# Sheet1.net
KiCad netlist of a schematic drawn in Altium Designer
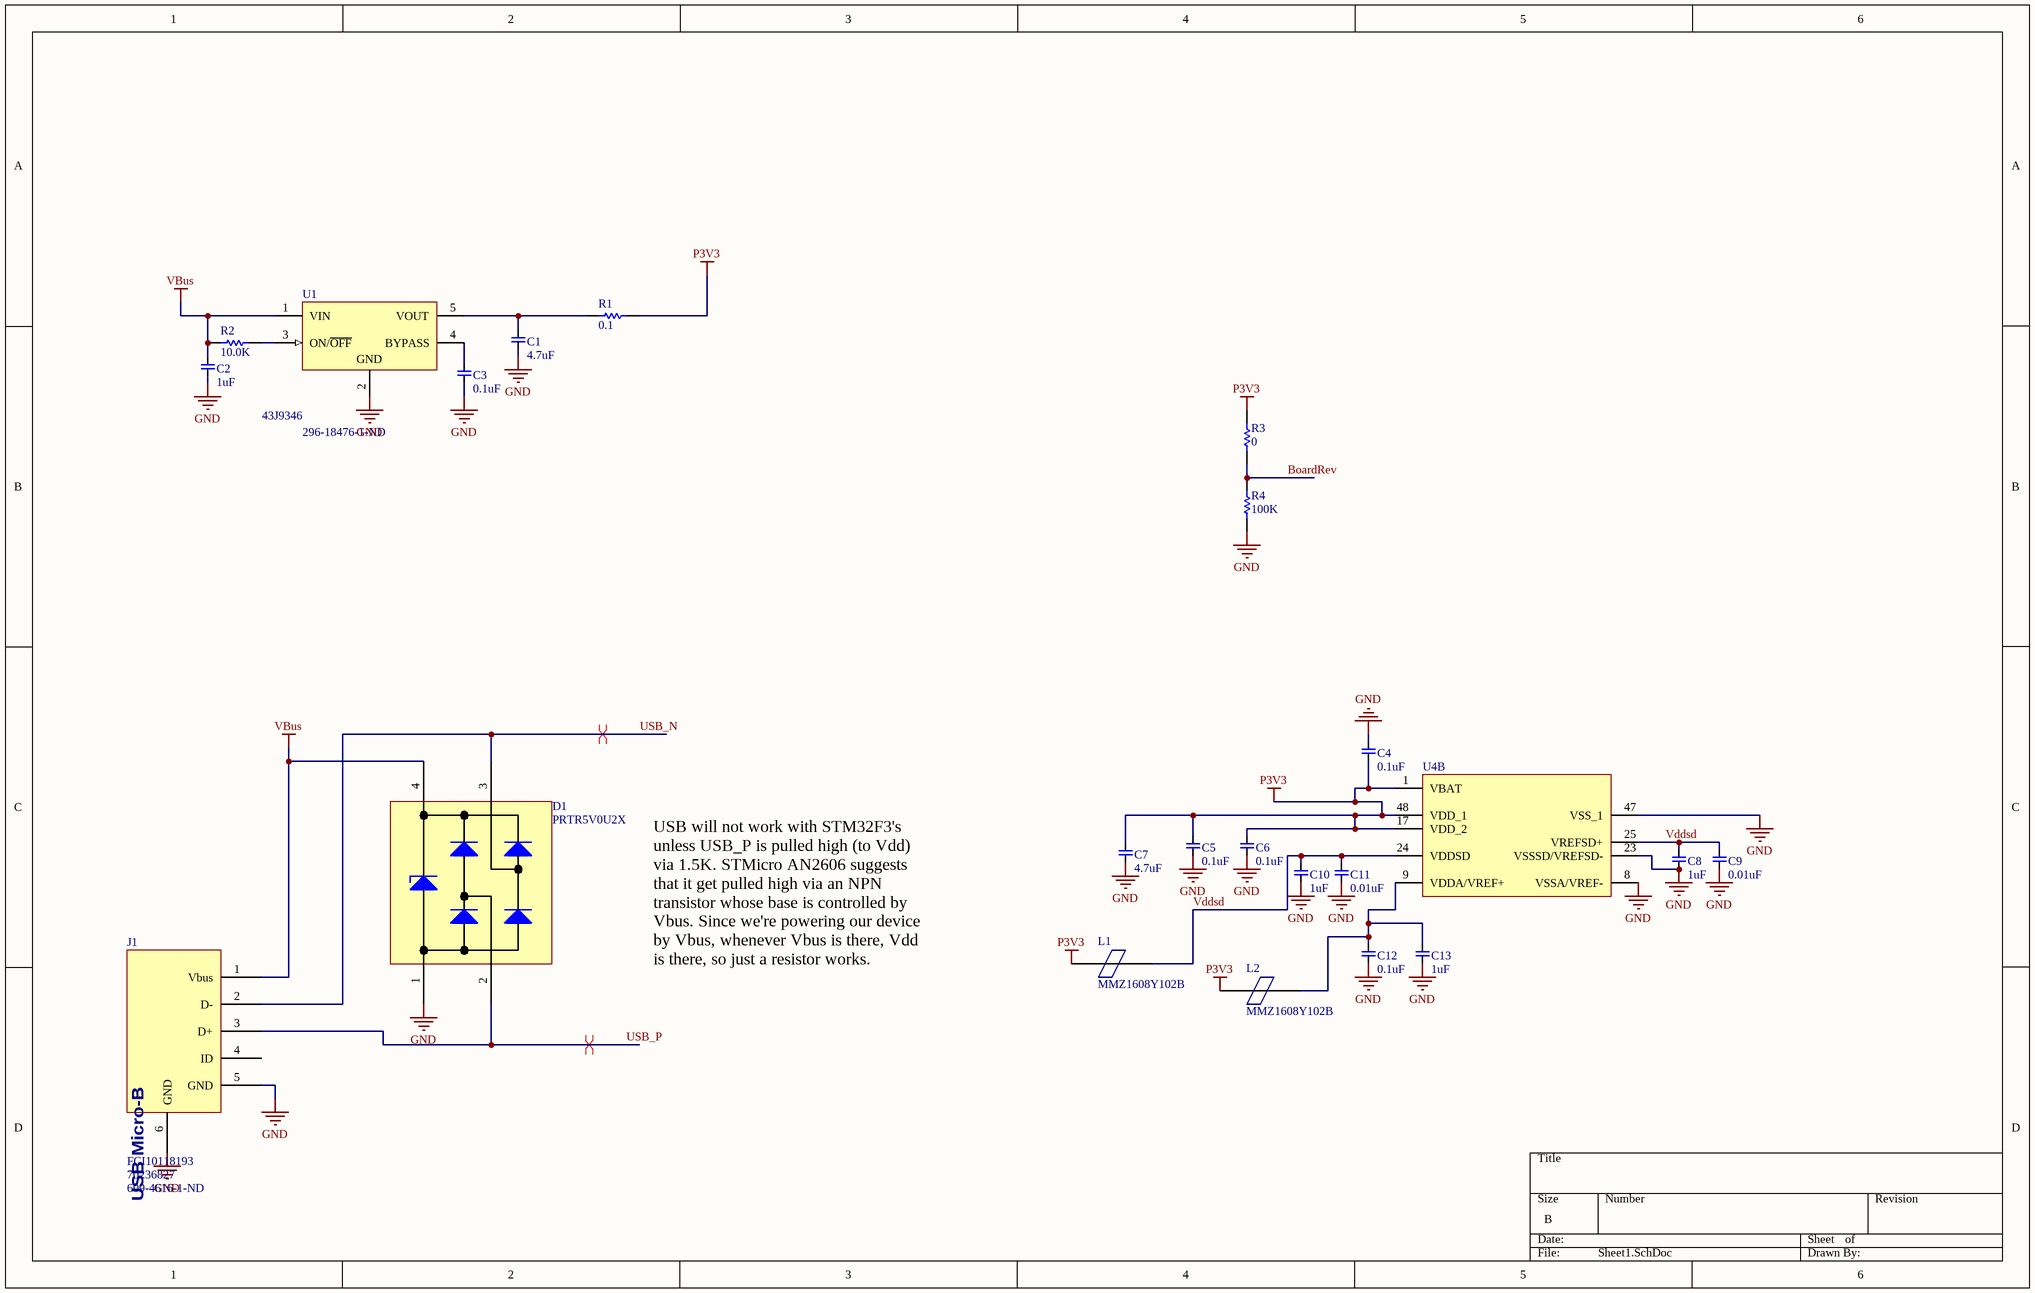
[diagram p0: Sheet1.SchDoc]

(export (version "E")
  (design (tool "Eeschema 10.0.6"))
  (components
    (comp (ref "C1")
      (value "4.7uF")
      (footprint "CAP0603")
      (description "CAP 4.7uF +/-10% 10V X6S 0603")
      (fields (field (name "TOLERANCE") "+/-10%") (field (name "VOLTAGE") "10V"))
      (libsource (lib "PassiveSMT") (part "Capacitor_np"))
    )
    (comp (ref "C2")
      (value "1uF")
      (footprint "CAP0402")
      (description "CAP 1uF +/-10% 10V X5R 0402")
      (fields (field (name "TOLERANCE") "+/-10%") (field (name "VOLTAGE") "10V"))
      (libsource (lib "PassiveSMT") (part "Capacitor_np"))
    )
    (comp (ref "C3")
      (value "0.1uF")
      (footprint "CAP0402")
      (description "CAP 0.1uF +/-10% 25V X7R 0402")
      (fields (field (name "TOLERANCE") "+/-10%") (field (name "VOLTAGE") "25V"))
      (libsource (lib "PassiveSMT") (part "Capacitor_np"))
    )
    (comp (ref "C4")
      (value "0.1uF")
      (footprint "CAP0402")
      (description "CAP 0.1uF +/-10% 25V X7R 0402")
      (fields (field (name "TOLERANCE") "+/-10%") (field (name "VOLTAGE") "25V"))
      (libsource (lib "PassiveSMT") (part "Capacitor_np"))
    )
    (comp (ref "C5")
      (value "0.1uF")
      (footprint "CAP0402")
      (description "CAP 0.1uF +/-10% 25V X7R 0402")
      (fields (field (name "TOLERANCE") "+/-10%") (field (name "VOLTAGE") "25V"))
      (libsource (lib "PassiveSMT") (part "Capacitor_np"))
    )
    (comp (ref "C6")
      (value "0.1uF")
      (footprint "CAP0402")
      (description "CAP 0.1uF +/-10% 25V X7R 0402")
      (fields (field (name "TOLERANCE") "+/-10%") (field (name "VOLTAGE") "25V"))
      (libsource (lib "PassiveSMT") (part "Capacitor_np"))
    )
    (comp (ref "C7")
      (value "4.7uF")
      (footprint "CAP0603")
      (description "CAP 4.7uF +/-10% 10V X6S 0603")
      (fields (field (name "TOLERANCE") "+/-10%") (field (name "VOLTAGE") "10V"))
      (libsource (lib "PassiveSMT") (part "Capacitor_np"))
    )
    (comp (ref "C8")
      (value "1uF")
      (footprint "CAP0603")
      (description "CAP 1uF +/-10% 25V X7R 0603")
      (fields (field (name "TOLERANCE") "+/-10%") (field (name "VOLTAGE") "25V"))
      (libsource (lib "PassiveSMT") (part "Capacitor_np"))
    )
    (comp (ref "C9")
      (value "0.01uF")
      (footprint "CAP0402")
      (description "CAP 0.01uF +/-20% 50V X6S 0402")
      (fields (field (name "TOLERANCE") "+/-20%") (field (name "VOLTAGE") "50V"))
      (libsource (lib "PassiveSMT") (part "Capacitor_np"))
    )
    (comp (ref "C10")
      (value "1uF")
      (footprint "CAP0603")
      (description "CAP 1uF +/-10% 25V X7R 0603")
      (fields (field (name "TOLERANCE") "+/-10%") (field (name "VOLTAGE") "25V"))
      (libsource (lib "PassiveSMT") (part "Capacitor_np"))
    )
    (comp (ref "C11")
      (value "0.01uF")
      (footprint "CAP0402")
      (description "CAP 0.01uF +/-20% 50V X6S 0402")
      (fields (field (name "TOLERANCE") "+/-20%") (field (name "VOLTAGE") "50V"))
      (libsource (lib "PassiveSMT") (part "Capacitor_np"))
    )
    (comp (ref "C12")
      (value "0.1uF")
      (footprint "CAP0402")
      (description "CAP 0.1uF +/-10% 25V X7R 0402")
      (fields (field (name "TOLERANCE") "+/-10%") (field (name "VOLTAGE") "25V"))
      (libsource (lib "PassiveSMT") (part "Capacitor_np"))
    )
    (comp (ref "C13")
      (value "1uF")
      (footprint "CAP0603")
      (description "CAP 1uF +/-10% 25V X7R 0603")
      (fields (field (name "TOLERANCE") "+/-10%") (field (name "VOLTAGE") "25V"))
      (libsource (lib "PassiveSMT") (part "Capacitor_np"))
    )
    (comp (ref "D1")
      (value "PRTR5V0U2X")
      (footprint "SOT190P230X110-4N")
      (description "Diode Array, ESD Protection 1pF USB2.0 SOT143")
      (fields (field (name "MANUFACTURER") "NXP Semiconductors"))
      (libsource (lib "MF_MiscLib") (part "PRTR5V0U2X"))
    )
    (comp (ref "J1")
      (value "FCI10118193")
      (footprint "FCI_10118193")
      (description "Connector Receptacle USB - micro B 2.0 5 Position Surface Mount, Right Angle, Horizontal")
      (fields
        (field (name "MANUFACTURER") "FCI")
        (field (name "SUPPLIER PART NUMBER 1") "70236827")
        (field (name "SUPPLIER PART NUMBER 2") "609-4616-1-ND")
      )
      (libsource (lib "MF_MiscLib") (part "CONN_USB_MICRO-B_HORIZ_TH"))
    )
    (comp (ref "L1")
      (value "MMZ1608Y102B")
      (footprint "INDC1608X06N")
      (description "Ferrite, 1000oh, 400mA, 0603")
      (libsource (lib "MF_MiscLib") (part "MMZ1608Y102B"))
    )
    (comp (ref "L2")
      (value "MMZ1608Y102B")
      (footprint "INDC1608X06N")
      (description "Ferrite, 1000oh, 400mA, 0603")
      (libsource (lib "MF_MiscLib") (part "MMZ1608Y102B"))
    )
    (comp (ref "R1")
      (value "0.1")
      (footprint "RES0402")
      (description "RES .1 OHM 1/6W 1% 0402 SMD")
      (fields (field (name "MANUFACTURER") "Panasonic"))
      (libsource (lib "MF_MiscLib") (part "0402_0.1ohm"))
    )
    (comp (ref "R2")
      (value "10.0K")
      (footprint "RES0402")
      (description "Resistor SMT 0402 10.0K 1% ohm")
      (fields (field (name "TOLERANCE") "1%") (field (name "POWER") "1/16W"))
      (libsource (lib "PassiveSMT") (part "Resistor1"))
    )
    (comp (ref "R3")
      (value "0")
      (footprint "RES0402")
      (description "Resistor SMT 0402 0 1% ohm")
      (fields (field (name "TOLERANCE") "1%") (field (name "POWER") "1/16W"))
      (libsource (lib "PassiveSMT") (part "Resistor1"))
    )
    (comp (ref "R4")
      (value "100K")
      (footprint "RES0402")
      (description "Resistor SMT 0402 100K 1% ohm")
      (fields (field (name "TOLERANCE") "1%") (field (name "POWER") "1/16W"))
      (libsource (lib "PassiveSMT") (part "Resistor1"))
    )
    (comp (ref "U1")
      (value "~")
      (footprint "TI-DBV5_N")
      (fields
        (field (name "MANUFACTURER") "Texas Instruments")
        (field (name "PARTNUMBER") "LP2985-33DBVR")
        (field (name "SUPPLIER PART NUMBER 1") "43J9346")
        (field (name "SUPPLIER PART NUMBER 2") "296-18476-1-ND")
      )
      (libsource (lib "MF_MiscLib") (part "LP2985-33DBVR"))
    )
    (comp (ref "U4")
      (value "~")
      (footprint "STM-LQFP48_N")
      (fields (field (name "PARTNUMBER") "STM32F373CCT6"))
      (libsource (lib "STMicroelectronics_STM32_F3") (part "STM32F373CCT6"))
    )
  )
  (nets
    (net (code "1") (name "/BoardRev") (class "Default")
      (node (ref "R3") (pin "1") (pinfunction "1_1") (pintype "passive"))
      (node (ref "R4") (pin "2") (pinfunction "2_2") (pintype "passive"))
    )
    (net (code "2") (name "/USB_N") (class "Default")
      (node (ref "D1") (pin "3") (pinfunction "3_3") (pintype "passive"))
      (node (ref "J1") (pin "2") (pinfunction "D-_2") (pintype "passive"))
    )
    (net (code "3") (name "/USB_P") (class "Default")
      (node (ref "D1") (pin "2") (pinfunction "2_2") (pintype "passive"))
      (node (ref "J1") (pin "3") (pinfunction "D+_3") (pintype "passive"))
    )
    (net (code "4") (name "/Vddsd") (class "Default")
      (node (ref "C10") (pin "2") (pinfunction "2_2") (pintype "passive"))
      (node (ref "C11") (pin "2") (pinfunction "2_2") (pintype "passive"))
      (node (ref "C8") (pin "2") (pinfunction "2_2") (pintype "passive"))
      (node (ref "C9") (pin "2") (pinfunction "2_2") (pintype "passive"))
      (node (ref "L1") (pin "2") (pinfunction "2_2") (pintype "passive"))
      (node (ref "U4") (pin "24") (pinfunction "VDDSD_24") (pintype "power_in"))
      (node (ref "U4") (pin "25") (pinfunction "VREFSD+_25") (pintype "power_in"))
    )
    (net (code "5") (name "GND") (class "Default")
      (node (ref "C1") (pin "1") (pinfunction "1_1") (pintype "passive"))
      (node (ref "C10") (pin "1") (pinfunction "1_1") (pintype "passive"))
      (node (ref "C11") (pin "1") (pinfunction "1_1") (pintype "passive"))
      (node (ref "C12") (pin "1") (pinfunction "1_1") (pintype "passive"))
      (node (ref "C13") (pin "1") (pinfunction "1_1") (pintype "passive"))
      (node (ref "C2") (pin "1") (pinfunction "1_1") (pintype "passive"))
      (node (ref "C3") (pin "1") (pinfunction "1_1") (pintype "passive"))
      (node (ref "C4") (pin "2") (pinfunction "2_2") (pintype "passive"))
      (node (ref "C5") (pin "1") (pinfunction "1_1") (pintype "passive"))
      (node (ref "C6") (pin "1") (pinfunction "1_1") (pintype "passive"))
      (node (ref "C7") (pin "1") (pinfunction "1_1") (pintype "passive"))
      (node (ref "C8") (pin "1") (pinfunction "1_1") (pintype "passive"))
      (node (ref "C9") (pin "1") (pinfunction "1_1") (pintype "passive"))
      (node (ref "D1") (pin "1") (pinfunction "1_1") (pintype "passive"))
      (node (ref "J1") (pin "5") (pinfunction "GND_5") (pintype "passive"))
      (node (ref "J1") (pin "6") (pinfunction "GND_6") (pintype "passive"))
      (node (ref "R4") (pin "1") (pinfunction "1_1") (pintype "passive"))
      (node (ref "U1") (pin "2") (pinfunction "GND_2") (pintype "power_in"))
      (node (ref "U4") (pin "23") (pinfunction "VSSSD/VREFSD-_23") (pintype "power_in"))
      (node (ref "U4") (pin "47") (pinfunction "VSS_1_47") (pintype "power_in"))
      (node (ref "U4") (pin "8") (pinfunction "VSSA/VREF-_8") (pintype "power_in"))
    )
    (net (code "6") (name "Net-(U1-BYPASS)") (class "Default")
      (node (ref "C3") (pin "2") (pinfunction "2_2") (pintype "passive"))
      (node (ref "U1") (pin "4") (pinfunction "BYPASS_4") (pintype "passive"))
    )
    (net (code "7") (name "Net-(U1-ON{slash}~{OFF})") (class "Default")
      (node (ref "R2") (pin "2") (pinfunction "2_2") (pintype "passive"))
      (node (ref "U1") (pin "3") (pinfunction "ON/~{OFF}_3") (pintype "input"))
    )
    (net (code "8") (name "Net-(U1-VOUT)") (class "Default")
      (node (ref "C1") (pin "2") (pinfunction "2_2") (pintype "passive"))
      (node (ref "R1") (pin "1") (pinfunction "1_1") (pintype "passive"))
      (node (ref "U1") (pin "5") (pinfunction "VOUT_5") (pintype "power_in"))
    )
    (net (code "9") (name "Net-(U4B-VDDA{slash}VREF+)") (class "Default")
      (node (ref "C12") (pin "2") (pinfunction "2_2") (pintype "passive"))
      (node (ref "C13") (pin "2") (pinfunction "2_2") (pintype "passive"))
      (node (ref "L2") (pin "2") (pinfunction "2_2") (pintype "passive"))
      (node (ref "U4") (pin "9") (pinfunction "VDDA/VREF+_9") (pintype "power_in"))
    )
    (net (code "10") (name "P3V3") (class "Default")
      (node (ref "C4") (pin "1") (pinfunction "1_1") (pintype "passive"))
      (node (ref "C5") (pin "2") (pinfunction "2_2") (pintype "passive"))
      (node (ref "C6") (pin "2") (pinfunction "2_2") (pintype "passive"))
      (node (ref "C7") (pin "2") (pinfunction "2_2") (pintype "passive"))
      (node (ref "L1") (pin "1") (pinfunction "1_1") (pintype "passive"))
      (node (ref "L2") (pin "1") (pinfunction "1_1") (pintype "passive"))
      (node (ref "R1") (pin "2") (pinfunction "2_2") (pintype "passive"))
      (node (ref "R3") (pin "2") (pinfunction "2_2") (pintype "passive"))
      (node (ref "U4") (pin "1") (pinfunction "VBAT_1") (pintype "power_in"))
      (node (ref "U4") (pin "17") (pinfunction "VDD_2_17") (pintype "power_in"))
      (node (ref "U4") (pin "48") (pinfunction "VDD_1_48") (pintype "power_in"))
    )
    (net (code "11") (name "VBus") (class "Default")
      (node (ref "C2") (pin "2") (pinfunction "2_2") (pintype "passive"))
      (node (ref "D1") (pin "4") (pinfunction "4_4") (pintype "passive"))
      (node (ref "J1") (pin "1") (pinfunction "Vbus_1") (pintype "passive"))
      (node (ref "R2") (pin "1") (pinfunction "1_1") (pintype "passive"))
      (node (ref "U1") (pin "1") (pinfunction "VIN_1") (pintype "power_in"))
    )
    (net (code "12") (name "unconnected-(J1-ID-Pad4)") (class "Default")
      (node (ref "J1") (pin "4") (pinfunction "ID_4") (pintype "passive"))
    )
  )
)
